# charger.net
KiCad netlist of a schematic drawn in Altium Designer
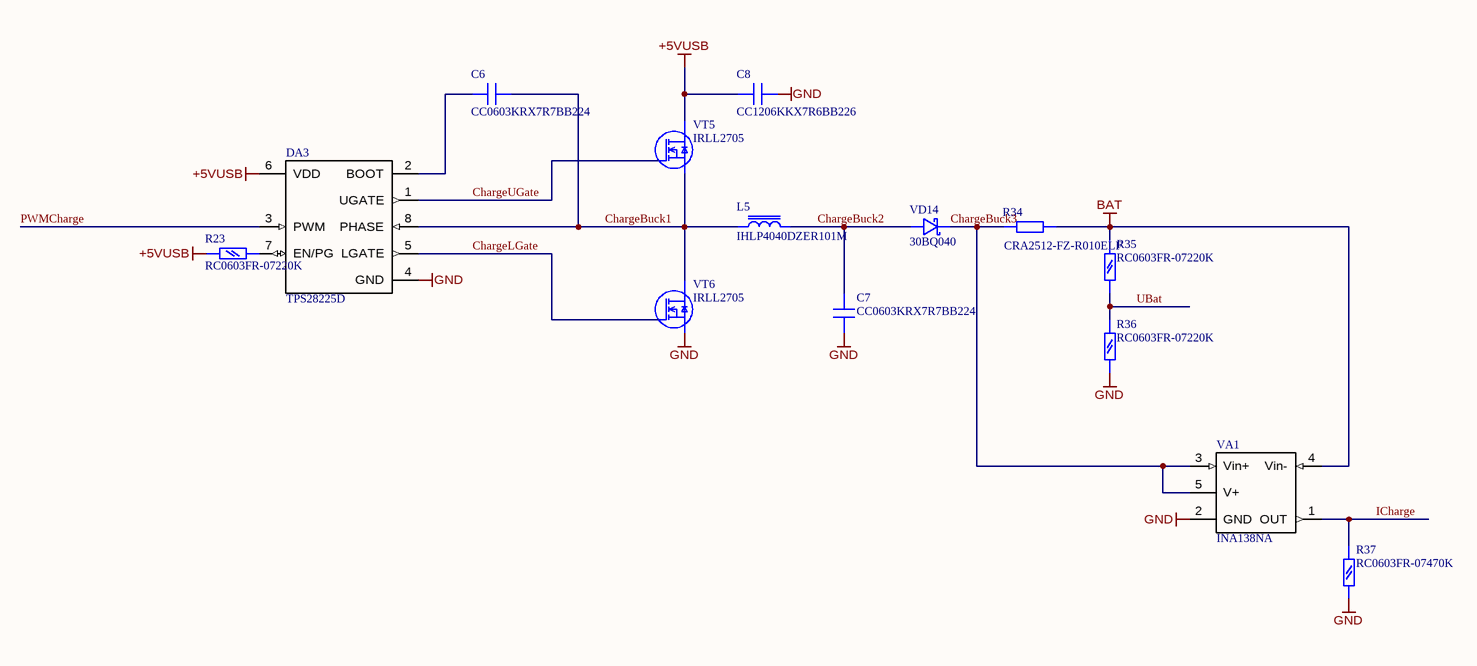
[diagram p0: charger.SchDoc]

(export (version "E")
  (design (tool "Eeschema 10.0.6"))
  (components
    (comp (ref "C6")
      (value "CC0603KRX7R7BB224")
      (footprint "CapacitorSMD0603(manual)")
      (description "CAPACITOR Capacitor SMD 0603 1.6x0.8mm")
      (libsource (lib "Integrated_Library") (part "CapacitorSMD0603(reflow)"))
    )
    (comp (ref "C7")
      (value "CC0603KRX7R7BB224")
      (footprint "CapacitorSMD0603(manual)")
      (description "CAPACITOR Capacitor SMD 0603 1.6x0.8mm")
      (libsource (lib "Integrated_Library") (part "CapacitorSMD0603(reflow)"))
    )
    (comp (ref "C8")
      (value "CC1206KKX7R6BB226")
      (footprint "CapacitorSMD1206(reflow)")
      (description "CAPACITOR Capacitor SMD 1206 3.2x1.6mm")
      (libsource (lib "Integrated_Library") (part "CapacitorSMD1206(reflow)"))
    )
    (comp (ref "DA3")
      (value "TPS28225D")
      (footprint "SO8")
      (description "IC Synchronous MOSFET drivers")
      (libsource (lib "Integrated_Library") (part "TPS28225D"))
    )
    (comp (ref "L5")
      (value "IHLP4040DZER101M")
      (footprint "IHLP-4040DZ(manual/deep1.5mm)")
      (description "MAGNETIC Inductor SMD 4040 h=4mm")
      (libsource (lib "Integrated_Library") (part "IHLP-4040DZ"))
    )
    (comp (ref "R23")
      (value "RC0603FR-07220K")
      (footprint "ResistorSMD0603(manual)")
      (description "RESISTOR Resistor SMD 0603 1.6x0.8mm")
      (libsource (lib "Integrated_Library") (part "ResistorSMD0603(reflow)"))
    )
    (comp (ref "R34")
      (value "CRA2512-FZ-R010ELF")
      (footprint "ResistorSMD2512(reflow)")
      (description "RESISTOR Resistor SMD 2512 6.35x3.2mm")
      (libsource (lib "Integrated_Library") (part "ResistorSMD2512(reflow)"))
    )
    (comp (ref "R35")
      (value "RC0603FR-07220K")
      (footprint "ResistorSMD0603(manual)")
      (description "RESISTOR Resistor SMD 0603 1.6x0.8mm")
      (libsource (lib "Integrated_Library") (part "ResistorSMD0603(reflow)"))
    )
    (comp (ref "R36")
      (value "RC0603FR-07220K")
      (footprint "ResistorSMD0603(manual)")
      (description "RESISTOR Resistor SMD 0603 1.6x0.8mm")
      (libsource (lib "Integrated_Library") (part "ResistorSMD0603(reflow)"))
    )
    (comp (ref "R37")
      (value "RC0603FR-07470K")
      (footprint "ResistorSMD0603(manual)")
      (description "RESISTOR Resistor SMD 0603 1.6x0.8mm")
      (libsource (lib "Integrated_Library") (part "ResistorSMD0603(reflow)"))
    )
    (comp (ref "VA1")
      (value "INA138NA")
      (footprint "SOT23-5")
      (description "IC High-Side Current Shunt Monitor 2.7...36V")
      (libsource (lib "Integrated_Library") (part "INA138NA"))
    )
    (comp (ref "VD14")
      (value "30BQ040")
      (footprint "SMC")
      (description "DIODE Schottky rectifier")
      (libsource (lib "Integrated_Library") (part "30BQ___"))
    )
    (comp (ref "VT5")
      (value "IRLL2705")
      (footprint "SOT223")
      (description "TRANSISTOR MOSFET N generic sot23")
      (libsource (lib "Integrated_Library") (part "MOSFET_N_SOT223"))
    )
    (comp (ref "VT6")
      (value "IRLL2705")
      (footprint "SOT223")
      (description "TRANSISTOR MOSFET N generic sot23")
      (libsource (lib "Integrated_Library") (part "MOSFET_N_SOT223"))
    )
  )
  (nets
    (net (code "1") (name "+5VUSB") (class "Default")
      (node (ref "C8") (pin "2") (pintype "passive"))
      (node (ref "DA3") (pin "6") (pinfunction "VDD_6") (pintype "power_in"))
      (node (ref "R23") (pin "1") (pinfunction "1_1") (pintype "passive"))
      (node (ref "VT5") (pin "2") (pinfunction "D_2") (pintype "passive"))
    )
    (net (code "2") (name "/ChargeBuck1") (class "Default")
      (node (ref "C6") (pin "2") (pintype "passive"))
      (node (ref "DA3") (pin "8") (pinfunction "PHASE_8") (pintype "input"))
      (node (ref "L5") (pin "1") (pintype "passive"))
      (node (ref "VT5") (pin "3") (pinfunction "S_3") (pintype "passive"))
      (node (ref "VT6") (pin "2") (pinfunction "D_2") (pintype "passive"))
    )
    (net (code "3") (name "/ChargeBuck2") (class "Default")
      (node (ref "C7") (pin "2") (pintype "passive"))
      (node (ref "L5") (pin "2") (pintype "passive"))
      (node (ref "VD14") (pin "1") (pintype "passive"))
    )
    (net (code "4") (name "/ChargeBuck3") (class "Default")
      (node (ref "R34") (pin "2") (pinfunction "2_2") (pintype "passive"))
      (node (ref "VA1") (pin "3") (pinfunction "Vin+_3") (pintype "input"))
      (node (ref "VA1") (pin "5") (pinfunction "V+_5") (pintype "power_in"))
      (node (ref "VD14") (pin "2") (pintype "passive"))
    )
    (net (code "5") (name "/ChargeLGate") (class "Default")
      (node (ref "DA3") (pin "5") (pinfunction "LGATE_5") (pintype "output"))
      (node (ref "VT6") (pin "1") (pinfunction "G_1") (pintype "passive"))
    )
    (net (code "6") (name "/ChargeUGate") (class "Default")
      (node (ref "DA3") (pin "1") (pinfunction "UGATE_1") (pintype "output"))
      (node (ref "VT5") (pin "1") (pinfunction "G_1") (pintype "passive"))
    )
    (net (code "7") (name "/ICharge") (class "Default")
      (node (ref "R37") (pin "2") (pinfunction "2_2") (pintype "passive"))
      (node (ref "VA1") (pin "1") (pinfunction "OUT_1") (pintype "output"))
    )
    (net (code "8") (name "/PWMCharge") (class "Default")
      (node (ref "DA3") (pin "3") (pinfunction "PWM_3") (pintype "input"))
    )
    (net (code "9") (name "/UBat") (class "Default")
      (node (ref "R35") (pin "1") (pinfunction "1_1") (pintype "passive"))
      (node (ref "R36") (pin "2") (pinfunction "2_2") (pintype "passive"))
    )
    (net (code "10") (name "BAT") (class "Default")
      (node (ref "R34") (pin "1") (pinfunction "1_1") (pintype "passive"))
      (node (ref "R35") (pin "2") (pinfunction "2_2") (pintype "passive"))
      (node (ref "VA1") (pin "4") (pinfunction "Vin-_4") (pintype "input"))
    )
    (net (code "11") (name "GND") (class "Default")
      (node (ref "C7") (pin "1") (pintype "passive"))
      (node (ref "C8") (pin "1") (pintype "passive"))
      (node (ref "DA3") (pin "4") (pinfunction "GND_4") (pintype "power_in"))
      (node (ref "R36") (pin "1") (pinfunction "1_1") (pintype "passive"))
      (node (ref "R37") (pin "1") (pinfunction "1_1") (pintype "passive"))
      (node (ref "VA1") (pin "2") (pinfunction "GND_2") (pintype "power_in"))
      (node (ref "VT6") (pin "3") (pinfunction "S_3") (pintype "passive"))
    )
    (net (code "12") (name "Net-(DA3-BOOT)") (class "Default")
      (node (ref "C6") (pin "1") (pintype "passive"))
      (node (ref "DA3") (pin "2") (pinfunction "BOOT_2") (pintype "power_in"))
    )
    (net (code "13") (name "Net-(DA3-EN{slash}PG)") (class "Default")
      (node (ref "DA3") (pin "7") (pinfunction "EN/PG_7") (pintype "bidirectional"))
      (node (ref "R23") (pin "2") (pinfunction "2_2") (pintype "passive"))
    )
  )
)
